# FinalSchematic1_0.net
KiCad netlist of a schematic drawn in EAGLE
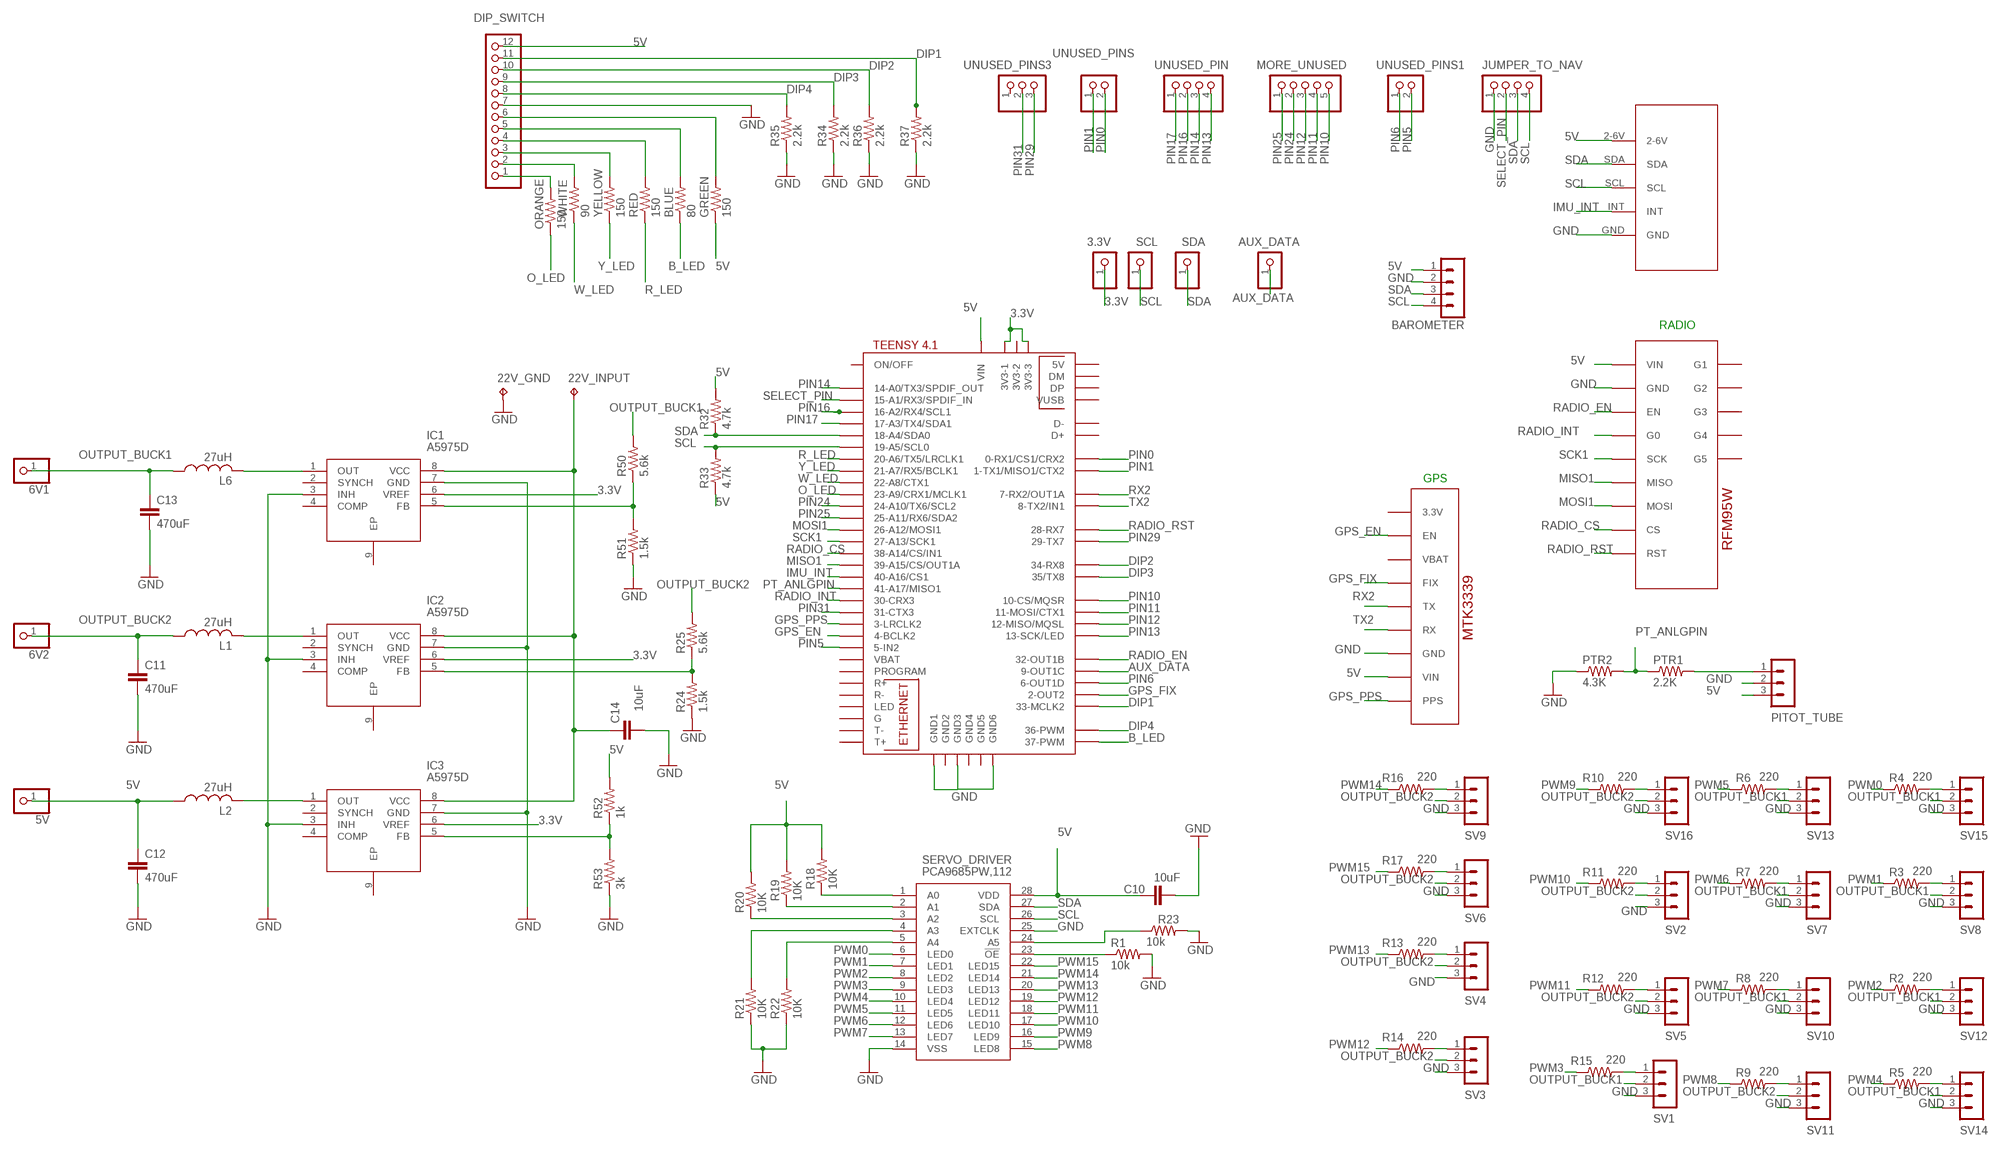
[diagram p0: schematic, sheet 1]

(export (version "E")
  (design (tool "Eeschema 10.0.6"))
  (components
    (comp (ref "3.3V")
      (value "PINHD-1X1")
      (footprint "eagle-import:1X01")
      (libsource (lib "eagle-import") (part "PINHD-1X1"))
    )
    (comp (ref "5V")
      (value "PINHD-1X1")
      (footprint "eagle-import:1X01")
      (libsource (lib "eagle-import") (part "PINHD-1X1"))
    )
    (comp (ref "6V1")
      (value "PINHD-1X1")
      (footprint "eagle-import:1X01")
      (libsource (lib "eagle-import") (part "PINHD-1X1"))
    )
    (comp (ref "6V2")
      (value "PINHD-1X1")
      (footprint "eagle-import:1X01")
      (libsource (lib "eagle-import") (part "PINHD-1X1"))
    )
    (comp (ref "22V_GND")
      (value "TPPAD1-17Y")
      (footprint "eagle-import:P1-17Y")
      (libsource (lib "eagle-import") (part "TPPAD1-17Y"))
    )
    (comp (ref "22V_INPUT")
      (value "TPPAD1-17Y")
      (footprint "eagle-import:P1-17Y")
      (libsource (lib "eagle-import") (part "TPPAD1-17Y"))
    )
    (comp (ref "AUX_DATA")
      (value "PINHD-1X1")
      (footprint "eagle-import:1X01")
      (libsource (lib "eagle-import") (part "PINHD-1X1"))
    )
    (comp (ref "BAROMETER")
      (value "MA04-1")
      (footprint "eagle-import:MA04-1")
      (libsource (lib "eagle-import") (part "MA04-1"))
    )
    (comp (ref "BLUE")
      (value "80")
      (footprint "eagle-import:0204_7")
      (libsource (lib "eagle-import") (part "R-US_0204/7"))
    )
    (comp (ref "C10")
      (value "10uF")
      (footprint "eagle-import:C2.5-3")
      (libsource (lib "eagle-import") (part "C2,5-3"))
    )
    (comp (ref "C11")
      (value "470uF")
      (footprint "eagle-import:C2.5-3")
      (libsource (lib "eagle-import") (part "C2,5-3"))
    )
    (comp (ref "C12")
      (value "470uF")
      (footprint "eagle-import:C2.5-3")
      (libsource (lib "eagle-import") (part "C2,5-3"))
    )
    (comp (ref "C13")
      (value "470uF")
      (footprint "eagle-import:C2.5-3")
      (libsource (lib "eagle-import") (part "C2,5-3"))
    )
    (comp (ref "C14")
      (value "10uF")
      (footprint "eagle-import:C2.5-3")
      (libsource (lib "eagle-import") (part "C2,5-3"))
    )
    (comp (ref "DIP_SWITCH")
      (value "PINHD-1X12")
      (footprint "eagle-import:1X12")
      (libsource (lib "eagle-import") (part "PINHD-1X12"))
    )
    (comp (ref "GPSMTK3339")
      (value "ADAFRUIT_MTK3339_GPS")
      (footprint "eagle-import:ADAFRUIT_MTK3339_GPS")
      (libsource (lib "eagle-import") (part "ADAFRUIT_MTK3339_GPS"))
    )
    (comp (ref "GREEN")
      (value "150")
      (footprint "eagle-import:0204_7")
      (libsource (lib "eagle-import") (part "R-US_0204/7"))
    )
    (comp (ref "IC1")
      (value "A5975D")
      (footprint "eagle-import:SOIC127P600X170-9N")
      (fields (field (name "MOUSER_PART_NUMBER") "511-A5975D"))
      (libsource (lib "eagle-import") (part "A5975D"))
    )
    (comp (ref "IC2")
      (value "A5975D")
      (footprint "eagle-import:SOIC127P600X170-9N")
      (fields (field (name "MOUSER_PART_NUMBER") "511-A5975D"))
      (libsource (lib "eagle-import") (part "A5975D"))
    )
    (comp (ref "IC3")
      (value "A5975D")
      (footprint "eagle-import:SOIC127P600X170-9N")
      (fields (field (name "MOUSER_PART_NUMBER") "511-A5975D"))
      (libsource (lib "eagle-import") (part "A5975D"))
    )
    (comp (ref "JUMPER_TO_NAV")
      (value "PINHD-1X4")
      (footprint "eagle-import:1X04")
      (libsource (lib "eagle-import") (part "PINHD-1X4"))
    )
    (comp (ref "L1")
      (value "27uH")
      (footprint "eagle-import:TFI0307")
      (libsource (lib "eagle-import") (part "L-USTFI0307"))
    )
    (comp (ref "L2")
      (value "27uH")
      (footprint "eagle-import:TFI0307")
      (libsource (lib "eagle-import") (part "L-USTFI0307"))
    )
    (comp (ref "L6")
      (value "27uH")
      (footprint "eagle-import:TFI0307")
      (libsource (lib "eagle-import") (part "L-USTFI0307"))
    )
    (comp (ref "MORE_UNUSED")
      (value "PINHD-1X5")
      (footprint "eagle-import:1X05")
      (libsource (lib "eagle-import") (part "PINHD-1X5"))
    )
    (comp (ref "ORANGE")
      (value "150")
      (footprint "eagle-import:0204_7")
      (libsource (lib "eagle-import") (part "R-US_0204/7"))
    )
    (comp (ref "PITOT_TUBE")
      (value "MA03-1")
      (footprint "eagle-import:MA03-1")
      (libsource (lib "eagle-import") (part "MA03-1"))
    )
    (comp (ref "PTR1")
      (value "2.2K")
      (footprint "eagle-import:0204_7")
      (libsource (lib "eagle-import") (part "R-US_0204/7"))
    )
    (comp (ref "PTR2")
      (value "4.3K")
      (footprint "eagle-import:0204_7")
      (libsource (lib "eagle-import") (part "R-US_0204/7"))
    )
    (comp (ref "R1")
      (value "10k")
      (footprint "eagle-import:0204_7")
      (libsource (lib "eagle-import") (part "R-US_0204/7"))
    )
    (comp (ref "R2")
      (value "220")
      (footprint "eagle-import:0204_7")
      (libsource (lib "eagle-import") (part "R-US_0204/7"))
    )
    (comp (ref "R3")
      (value "220")
      (footprint "eagle-import:0204_7")
      (libsource (lib "eagle-import") (part "R-US_0204/7"))
    )
    (comp (ref "R4")
      (value "220")
      (footprint "eagle-import:0204_7")
      (libsource (lib "eagle-import") (part "R-US_0204/7"))
    )
    (comp (ref "R5")
      (value "220")
      (footprint "eagle-import:0204_7")
      (libsource (lib "eagle-import") (part "R-US_0204/7"))
    )
    (comp (ref "R6")
      (value "220")
      (footprint "eagle-import:0204_7")
      (libsource (lib "eagle-import") (part "R-US_0204/7"))
    )
    (comp (ref "R7")
      (value "220")
      (footprint "eagle-import:0204_7")
      (libsource (lib "eagle-import") (part "R-US_0204/7"))
    )
    (comp (ref "R8")
      (value "220")
      (footprint "eagle-import:0204_7")
      (libsource (lib "eagle-import") (part "R-US_0204/7"))
    )
    (comp (ref "R9")
      (value "220")
      (footprint "eagle-import:0204_7")
      (libsource (lib "eagle-import") (part "R-US_0204/7"))
    )
    (comp (ref "R10")
      (value "220")
      (footprint "eagle-import:0204_7")
      (libsource (lib "eagle-import") (part "R-US_0204/7"))
    )
    (comp (ref "R11")
      (value "220")
      (footprint "eagle-import:0204_7")
      (libsource (lib "eagle-import") (part "R-US_0204/7"))
    )
    (comp (ref "R12")
      (value "220")
      (footprint "eagle-import:0204_7")
      (libsource (lib "eagle-import") (part "R-US_0204/7"))
    )
    (comp (ref "R13")
      (value "220")
      (footprint "eagle-import:0204_7")
      (libsource (lib "eagle-import") (part "R-US_0204/7"))
    )
    (comp (ref "R14")
      (value "220")
      (footprint "eagle-import:0204_7")
      (libsource (lib "eagle-import") (part "R-US_0204/7"))
    )
    (comp (ref "R15")
      (value "220")
      (footprint "eagle-import:0204_7")
      (libsource (lib "eagle-import") (part "R-US_0204/7"))
    )
    (comp (ref "R16")
      (value "220")
      (footprint "eagle-import:0204_7")
      (libsource (lib "eagle-import") (part "R-US_0204/7"))
    )
    (comp (ref "R17")
      (value "220")
      (footprint "eagle-import:0204_7")
      (libsource (lib "eagle-import") (part "R-US_0204/7"))
    )
    (comp (ref "R18")
      (value "10K")
      (footprint "eagle-import:0204_7")
      (libsource (lib "eagle-import") (part "R-US_0204/7"))
    )
    (comp (ref "R19")
      (value "10K")
      (footprint "eagle-import:0204_7")
      (libsource (lib "eagle-import") (part "R-US_0204/7"))
    )
    (comp (ref "R20")
      (value "10K")
      (footprint "eagle-import:0204_7")
      (libsource (lib "eagle-import") (part "R-US_0204/7"))
    )
    (comp (ref "R21")
      (value "10K")
      (footprint "eagle-import:0204_7")
      (libsource (lib "eagle-import") (part "R-US_0204/7"))
    )
    (comp (ref "R22")
      (value "10K")
      (footprint "eagle-import:0204_7")
      (libsource (lib "eagle-import") (part "R-US_0204/7"))
    )
    (comp (ref "R23")
      (value "10k")
      (footprint "eagle-import:0204_7")
      (libsource (lib "eagle-import") (part "R-US_0204/7"))
    )
    (comp (ref "R24")
      (value "1.5k")
      (footprint "eagle-import:0204_7")
      (libsource (lib "eagle-import") (part "R-US_0204/7"))
    )
    (comp (ref "R25")
      (value "5.6k")
      (footprint "eagle-import:0204_7")
      (libsource (lib "eagle-import") (part "R-US_0204/7"))
    )
    (comp (ref "R32")
      (value "4.7k")
      (footprint "eagle-import:0204_7")
      (libsource (lib "eagle-import") (part "R-US_0204/7"))
    )
    (comp (ref "R33")
      (value "4.7k")
      (footprint "eagle-import:0204_7")
      (libsource (lib "eagle-import") (part "R-US_0204/7"))
    )
    (comp (ref "R34")
      (value "2.2k")
      (footprint "eagle-import:0204_7")
      (libsource (lib "eagle-import") (part "R-US_0204/7"))
    )
    (comp (ref "R35")
      (value "2.2k")
      (footprint "eagle-import:0204_7")
      (libsource (lib "eagle-import") (part "R-US_0204/7"))
    )
    (comp (ref "R36")
      (value "2.2k")
      (footprint "eagle-import:0204_7")
      (libsource (lib "eagle-import") (part "R-US_0204/7"))
    )
    (comp (ref "R37")
      (value "2.2k")
      (footprint "eagle-import:0204_7")
      (libsource (lib "eagle-import") (part "R-US_0204/7"))
    )
    (comp (ref "R50")
      (value "5.6k")
      (footprint "eagle-import:0204_7")
      (libsource (lib "eagle-import") (part "R-US_0204/7"))
    )
    (comp (ref "R51")
      (value "1.5k")
      (footprint "eagle-import:0204_7")
      (libsource (lib "eagle-import") (part "R-US_0204/7"))
    )
    (comp (ref "R52")
      (value "1k")
      (footprint "eagle-import:0204_7")
      (libsource (lib "eagle-import") (part "R-US_0204/7"))
    )
    (comp (ref "R53")
      (value "3k")
      (footprint "eagle-import:0204_7")
      (libsource (lib "eagle-import") (part "R-US_0204/7"))
    )
    (comp (ref "RADIO")
      (value "ADAFRUIT_RFM95W_LORA_RADIO")
      (footprint "eagle-import:ADAFRUIT_RFM95W_LORA_RADIO")
      (libsource (lib "eagle-import") (part "ADAFRUIT_RFM95W_LORA_RADIO"))
    )
    (comp (ref "RED")
      (value "150")
      (footprint "eagle-import:0204_7")
      (libsource (lib "eagle-import") (part "R-US_0204/7"))
    )
    (comp (ref "SCL")
      (value "PINHD-1X1")
      (footprint "eagle-import:1X01")
      (libsource (lib "eagle-import") (part "PINHD-1X1"))
    )
    (comp (ref "SDA")
      (value "PINHD-1X1")
      (footprint "eagle-import:1X01")
      (libsource (lib "eagle-import") (part "PINHD-1X1"))
    )
    (comp (ref "SERVO_DRIVER")
      (value "PCA9685PW,112")
      (footprint "eagle-import:SOP65P640X110-28N")
      (fields (field (name "MOUSER_PART_NUMBER") "771-PCA9685PW,112"))
      (libsource (lib "eagle-import") (part "PCA9685PW,112"))
    )
    (comp (ref "SV1")
      (value "MA03-1")
      (footprint "eagle-import:MA03-1")
      (libsource (lib "eagle-import") (part "MA03-1"))
    )
    (comp (ref "SV2")
      (value "MA03-1")
      (footprint "eagle-import:MA03-1")
      (libsource (lib "eagle-import") (part "MA03-1"))
    )
    (comp (ref "SV3")
      (value "MA03-1")
      (footprint "eagle-import:MA03-1")
      (libsource (lib "eagle-import") (part "MA03-1"))
    )
    (comp (ref "SV4")
      (value "MA03-1")
      (footprint "eagle-import:MA03-1")
      (libsource (lib "eagle-import") (part "MA03-1"))
    )
    (comp (ref "SV5")
      (value "MA03-1")
      (footprint "eagle-import:MA03-1")
      (libsource (lib "eagle-import") (part "MA03-1"))
    )
    (comp (ref "SV6")
      (value "MA03-1")
      (footprint "eagle-import:MA03-1")
      (libsource (lib "eagle-import") (part "MA03-1"))
    )
    (comp (ref "SV7")
      (value "MA03-1")
      (footprint "eagle-import:MA03-1")
      (libsource (lib "eagle-import") (part "MA03-1"))
    )
    (comp (ref "SV8")
      (value "MA03-1")
      (footprint "eagle-import:MA03-1")
      (libsource (lib "eagle-import") (part "MA03-1"))
    )
    (comp (ref "SV9")
      (value "MA03-1")
      (footprint "eagle-import:MA03-1")
      (libsource (lib "eagle-import") (part "MA03-1"))
    )
    (comp (ref "SV10")
      (value "MA03-1")
      (footprint "eagle-import:MA03-1")
      (libsource (lib "eagle-import") (part "MA03-1"))
    )
    (comp (ref "SV11")
      (value "MA03-1")
      (footprint "eagle-import:MA03-1")
      (libsource (lib "eagle-import") (part "MA03-1"))
    )
    (comp (ref "SV12")
      (value "MA03-1")
      (footprint "eagle-import:MA03-1")
      (libsource (lib "eagle-import") (part "MA03-1"))
    )
    (comp (ref "SV13")
      (value "MA03-1")
      (footprint "eagle-import:MA03-1")
      (libsource (lib "eagle-import") (part "MA03-1"))
    )
    (comp (ref "SV14")
      (value "MA03-1")
      (footprint "eagle-import:MA03-1")
      (libsource (lib "eagle-import") (part "MA03-1"))
    )
    (comp (ref "SV15")
      (value "MA03-1")
      (footprint "eagle-import:MA03-1")
      (libsource (lib "eagle-import") (part "MA03-1"))
    )
    (comp (ref "SV16")
      (value "MA03-1")
      (footprint "eagle-import:MA03-1")
      (libsource (lib "eagle-import") (part "MA03-1"))
    )
    (comp (ref "TEENSY4.1")
      (value "TEENSY41")
      (footprint "eagle-import:TEENSY41")
      (libsource (lib "eagle-import") (part "TEENSY41"))
    )
    (comp (ref "U$2")
      (value "ICM20948BREAKOUTDEVICE")
      (footprint "eagle-import:ICM20948BREAKOUT")
      (libsource (lib "eagle-import") (part "ICM20948BREAKOUTDEVICE"))
    )
    (comp (ref "UNUSED_PIN")
      (value "PINHD-1X4")
      (footprint "eagle-import:1X04")
      (libsource (lib "eagle-import") (part "PINHD-1X4"))
    )
    (comp (ref "UNUSED_PINS")
      (value "PINHD-1X2")
      (footprint "eagle-import:1X02")
      (libsource (lib "eagle-import") (part "PINHD-1X2"))
    )
    (comp (ref "UNUSED_PINS1")
      (value "PINHD-1X2")
      (footprint "eagle-import:1X02")
      (libsource (lib "eagle-import") (part "PINHD-1X2"))
    )
    (comp (ref "UNUSED_PINS3")
      (value "PINHD-1X3")
      (footprint "eagle-import:1X03")
      (libsource (lib "eagle-import") (part "PINHD-1X3"))
    )
    (comp (ref "WHITE")
      (value "90")
      (footprint "eagle-import:0204_7")
      (libsource (lib "eagle-import") (part "R-US_0204/7"))
    )
    (comp (ref "YELLOW")
      (value "150")
      (footprint "eagle-import:0204_7")
      (libsource (lib "eagle-import") (part "R-US_0204/7"))
    )
  )
  (nets
    (net (code "1") (name "/3.3V") (class "Default")
      (node (ref "3.3V") (pin "1") (pinfunction "1_1") (pintype "passive"))
      (node (ref "IC1") (pin "6") (pinfunction "VREF_6") (pintype "bidirectional"))
      (node (ref "IC2") (pin "6") (pinfunction "VREF_6") (pintype "bidirectional"))
      (node (ref "IC3") (pin "6") (pinfunction "VREF_6") (pintype "bidirectional"))
      (node (ref "TEENSY4.1") (pin "3V3-1") (pinfunction "3V3-1_3V3-1") (pintype "bidirectional"))
      (node (ref "TEENSY4.1") (pin "3V3-3") (pinfunction "3V3-3_3V3-3") (pintype "bidirectional"))
    )
    (net (code "2") (name "/5V") (class "Default")
      (node (ref "5V") (pin "1") (pinfunction "1_1") (pintype "passive"))
      (node (ref "BAROMETER") (pin "1") (pinfunction "1_1") (pintype "passive"))
      (node (ref "C10") (pin "1") (pinfunction "1_1") (pintype "passive"))
      (node (ref "C12") (pin "1") (pinfunction "1_1") (pintype "passive"))
      (node (ref "DIP_SWITCH") (pin "12") (pinfunction "12_12") (pintype "passive"))
      (node (ref "GPSMTK3339") (pin "VIN") (pinfunction "VIN_VIN") (pintype "bidirectional"))
      (node (ref "GREEN") (pin "1") (pinfunction "1_1") (pintype "passive"))
      (node (ref "L2") (pin "1") (pinfunction "1_1") (pintype "passive"))
      (node (ref "PITOT_TUBE") (pin "3") (pinfunction "3_3") (pintype "passive"))
      (node (ref "R18") (pin "2") (pinfunction "2_2") (pintype "passive"))
      (node (ref "R19") (pin "2") (pinfunction "2_2") (pintype "passive"))
      (node (ref "R20") (pin "2") (pinfunction "2_2") (pintype "passive"))
      (node (ref "R32") (pin "2") (pinfunction "2_2") (pintype "passive"))
      (node (ref "R33") (pin "1") (pinfunction "1_1") (pintype "passive"))
      (node (ref "R52") (pin "2") (pinfunction "2_2") (pintype "passive"))
      (node (ref "RADIO") (pin "1") (pinfunction "VIN_1") (pintype "bidirectional"))
      (node (ref "SERVO_DRIVER") (pin "28") (pinfunction "VDD_28") (pintype "bidirectional"))
      (node (ref "TEENSY4.1") (pin "VIN") (pinfunction "VIN_VIN") (pintype "bidirectional"))
      (node (ref "U$2") (pin "2-6V") (pinfunction "2-6V_2-6V") (pintype "bidirectional"))
    )
    (net (code "3") (name "/AUX_DATA") (class "Default")
      (node (ref "AUX_DATA") (pin "1") (pinfunction "1_1") (pintype "passive"))
      (node (ref "TEENSY4.1") (pin "9-OUT1C") (pinfunction "9-OUT1C_9-OUT1C") (pintype "bidirectional"))
    )
    (net (code "4") (name "/B_LED") (class "Default")
      (node (ref "BLUE") (pin "1") (pinfunction "1_1") (pintype "passive"))
      (node (ref "TEENSY4.1") (pin "37-PWM") (pinfunction "37-PWM_37-PWM") (pintype "bidirectional"))
    )
    (net (code "5") (name "/DIP1") (class "Default")
      (node (ref "DIP_SWITCH") (pin "11") (pinfunction "11_11") (pintype "passive"))
      (node (ref "R37") (pin "2") (pinfunction "2_2") (pintype "passive"))
      (node (ref "TEENSY4.1") (pin "33-MCLK2") (pinfunction "33-MCLK2_33-MCLK2") (pintype "bidirectional"))
    )
    (net (code "6") (name "/DIP2") (class "Default")
      (node (ref "DIP_SWITCH") (pin "10") (pinfunction "10_10") (pintype "passive"))
      (node (ref "R36") (pin "2") (pinfunction "2_2") (pintype "passive"))
      (node (ref "TEENSY4.1") (pin "34-RX8") (pinfunction "34-RX8_34-RX8") (pintype "bidirectional"))
    )
    (net (code "7") (name "/DIP3") (class "Default")
      (node (ref "DIP_SWITCH") (pin "9") (pinfunction "9_9") (pintype "passive"))
      (node (ref "R34") (pin "2") (pinfunction "2_2") (pintype "passive"))
      (node (ref "TEENSY4.1") (pin "35-TX8") (pinfunction "35/TX8_35-TX8") (pintype "bidirectional"))
    )
    (net (code "8") (name "/DIP4") (class "Default")
      (node (ref "DIP_SWITCH") (pin "8") (pinfunction "8_8") (pintype "passive"))
      (node (ref "R35") (pin "2") (pinfunction "2_2") (pintype "passive"))
      (node (ref "TEENSY4.1") (pin "36-PWM") (pinfunction "36-PWM_36-PWM") (pintype "bidirectional"))
    )
    (net (code "9") (name "/GPS_EN") (class "Default")
      (node (ref "GPSMTK3339") (pin "EN") (pinfunction "EN_EN") (pintype "bidirectional"))
      (node (ref "TEENSY4.1") (pin "4-BCLK2") (pinfunction "4-BCLK2_4-BCLK2") (pintype "bidirectional"))
    )
    (net (code "10") (name "/GPS_FIX") (class "Default")
      (node (ref "GPSMTK3339") (pin "FIX") (pinfunction "FIX_FIX") (pintype "bidirectional"))
      (node (ref "TEENSY4.1") (pin "2-OUT2") (pinfunction "2-OUT2_2-OUT2") (pintype "bidirectional"))
    )
    (net (code "11") (name "/GPS_PPS") (class "Default")
      (node (ref "GPSMTK3339") (pin "PPS") (pinfunction "PPS_PPS") (pintype "bidirectional"))
      (node (ref "TEENSY4.1") (pin "3-LRCLK2") (pinfunction "3-LRCLK2_3-LRCLK2") (pintype "bidirectional"))
    )
    (net (code "12") (name "/IMU_INT") (class "Default")
      (node (ref "TEENSY4.1") (pin "40-A16/CS1") (pinfunction "40-A16/CS1_40-A16/CS1") (pintype "bidirectional"))
      (node (ref "U$2") (pin "INT") (pinfunction "INT_INT") (pintype "bidirectional"))
    )
    (net (code "13") (name "/MISO1") (class "Default")
      (node (ref "RADIO") (pin "6") (pinfunction "MISO_6") (pintype "bidirectional"))
      (node (ref "TEENSY4.1") (pin "39-A15/CS/OUT1A") (pinfunction "39-A15/CS/OUT1A_39-A15/CS/OUT1A") (pintype "bidirectional"))
    )
    (net (code "14") (name "/MOSI1") (class "Default")
      (node (ref "RADIO") (pin "7") (pinfunction "MOSI_7") (pintype "bidirectional"))
      (node (ref "TEENSY4.1") (pin "26-A12/MOSI1") (pinfunction "26-A12/MOSI1_26-A12/MOSI1") (pintype "bidirectional"))
    )
    (net (code "15") (name "/OUTPUT_BUCK1") (class "Default")
      (node (ref "6V1") (pin "1") (pinfunction "1_1") (pintype "passive"))
      (node (ref "C13") (pin "1") (pinfunction "1_1") (pintype "passive"))
      (node (ref "L6") (pin "1") (pinfunction "1_1") (pintype "passive"))
      (node (ref "R50") (pin "2") (pinfunction "2_2") (pintype "passive"))
      (node (ref "SV1") (pin "2") (pinfunction "2_2") (pintype "passive"))
      (node (ref "SV10") (pin "2") (pinfunction "2_2") (pintype "passive"))
      (node (ref "SV12") (pin "2") (pinfunction "2_2") (pintype "passive"))
      (node (ref "SV13") (pin "2") (pinfunction "2_2") (pintype "passive"))
      (node (ref "SV14") (pin "2") (pinfunction "2_2") (pintype "passive"))
      (node (ref "SV15") (pin "2") (pinfunction "2_2") (pintype "passive"))
      (node (ref "SV7") (pin "2") (pinfunction "2_2") (pintype "passive"))
      (node (ref "SV8") (pin "2") (pinfunction "2_2") (pintype "passive"))
    )
    (net (code "16") (name "/OUTPUT_BUCK2") (class "Default")
      (node (ref "6V2") (pin "1") (pinfunction "1_1") (pintype "passive"))
      (node (ref "C11") (pin "1") (pinfunction "1_1") (pintype "passive"))
      (node (ref "L1") (pin "1") (pinfunction "1_1") (pintype "passive"))
      (node (ref "R25") (pin "2") (pinfunction "2_2") (pintype "passive"))
      (node (ref "SV11") (pin "2") (pinfunction "2_2") (pintype "passive"))
      (node (ref "SV16") (pin "2") (pinfunction "2_2") (pintype "passive"))
      (node (ref "SV2") (pin "2") (pinfunction "2_2") (pintype "passive"))
      (node (ref "SV3") (pin "2") (pinfunction "2_2") (pintype "passive"))
      (node (ref "SV4") (pin "2") (pinfunction "2_2") (pintype "passive"))
      (node (ref "SV5") (pin "2") (pinfunction "2_2") (pintype "passive"))
      (node (ref "SV6") (pin "2") (pinfunction "2_2") (pintype "passive"))
      (node (ref "SV9") (pin "2") (pinfunction "2_2") (pintype "passive"))
    )
    (net (code "17") (name "/O_LED") (class "Default")
      (node (ref "ORANGE") (pin "1") (pinfunction "1_1") (pintype "passive"))
      (node (ref "TEENSY4.1") (pin "23-A9/CRX1/MCLK1") (pinfunction "23-A9/CRX1/MCLK1_23-A9/CRX1/MCLK1") (pintype "bidirectional"))
    )
    (net (code "18") (name "/PIN0") (class "Default")
      (node (ref "TEENSY4.1") (pin "0-RX1/CS1/CRX2") (pinfunction "0-RX1/CS1/CRX2_0-RX1/CS1/CRX2") (pintype "bidirectional"))
      (node (ref "UNUSED_PINS") (pin "2") (pinfunction "2_2") (pintype "passive"))
    )
    (net (code "19") (name "/PIN1") (class "Default")
      (node (ref "TEENSY4.1") (pin "1-TX1/MISO1/CTX2") (pinfunction "1-TX1/MISO1/CTX2_1-TX1/MISO1/CTX2") (pintype "bidirectional"))
      (node (ref "UNUSED_PINS") (pin "1") (pinfunction "1_1") (pintype "passive"))
    )
    (net (code "20") (name "/PIN5") (class "Default")
      (node (ref "TEENSY4.1") (pin "5-IN2") (pinfunction "5-IN2_5-IN2") (pintype "bidirectional"))
      (node (ref "UNUSED_PINS1") (pin "2") (pinfunction "2_2") (pintype "passive"))
    )
    (net (code "21") (name "/PIN6") (class "Default")
      (node (ref "TEENSY4.1") (pin "6-OUT1D") (pinfunction "6-OUT1D_6-OUT1D") (pintype "bidirectional"))
      (node (ref "UNUSED_PINS1") (pin "1") (pinfunction "1_1") (pintype "passive"))
    )
    (net (code "22") (name "/PIN10") (class "Default")
      (node (ref "MORE_UNUSED") (pin "5") (pinfunction "5_5") (pintype "passive"))
      (node (ref "TEENSY4.1") (pin "10-CS\\MQSR") (pinfunction "10-CS/MQSR_10-CS\\MQSR") (pintype "bidirectional"))
    )
    (net (code "23") (name "/PIN11") (class "Default")
      (node (ref "MORE_UNUSED") (pin "4") (pinfunction "4_4") (pintype "passive"))
      (node (ref "TEENSY4.1") (pin "11-MOSI/CTX1") (pinfunction "11-MOSI/CTX1_11-MOSI/CTX1") (pintype "bidirectional"))
    )
    (net (code "24") (name "/PIN12") (class "Default")
      (node (ref "MORE_UNUSED") (pin "3") (pinfunction "3_3") (pintype "passive"))
      (node (ref "TEENSY4.1") (pin "12-MISO/MQSL") (pinfunction "12-MISO/MQSL_12-MISO/MQSL") (pintype "bidirectional"))
    )
    (net (code "25") (name "/PIN13") (class "Default")
      (node (ref "TEENSY4.1") (pin "13-SCK/LED") (pinfunction "13-SCK/LED_13-SCK/LED") (pintype "bidirectional"))
      (node (ref "UNUSED_PIN") (pin "4") (pinfunction "4_4") (pintype "passive"))
    )
    (net (code "26") (name "/PIN14") (class "Default")
      (node (ref "TEENSY4.1") (pin "14-A0/TX3/SPDIF_OUT") (pinfunction "14-A0/TX3/SPDIF_OUT_14-A0/TX3/SPDIF_OUT") (pintype "bidirectional"))
      (node (ref "UNUSED_PIN") (pin "3") (pinfunction "3_3") (pintype "passive"))
    )
    (net (code "27") (name "/PIN16") (class "Default")
      (node (ref "TEENSY4.1") (pin "16-A2/RX4/SCL1") (pinfunction "16-A2/RX4/SCL1_16-A2/RX4/SCL1") (pintype "bidirectional"))
      (node (ref "UNUSED_PIN") (pin "2") (pinfunction "2_2") (pintype "passive"))
    )
    (net (code "28") (name "/PIN17") (class "Default")
      (node (ref "TEENSY4.1") (pin "17-A3/TX4/SDA1") (pinfunction "17-A3/TX4/SDA1_17-A3/TX4/SDA1") (pintype "bidirectional"))
      (node (ref "UNUSED_PIN") (pin "1") (pinfunction "1_1") (pintype "passive"))
    )
    (net (code "29") (name "/PIN24") (class "Default")
      (node (ref "MORE_UNUSED") (pin "2") (pinfunction "2_2") (pintype "passive"))
      (node (ref "TEENSY4.1") (pin "24-A10/TX6/SCL2") (pinfunction "24-A10/TX6/SCL2_24-A10/TX6/SCL2") (pintype "bidirectional"))
    )
    (net (code "30") (name "/PIN25") (class "Default")
      (node (ref "MORE_UNUSED") (pin "1") (pinfunction "1_1") (pintype "passive"))
      (node (ref "TEENSY4.1") (pin "25-A11/RX6/SDA2") (pinfunction "25-A11/RX6/SDA2_25-A11/RX6/SDA2") (pintype "bidirectional"))
    )
    (net (code "31") (name "/PIN29") (class "Default")
      (node (ref "TEENSY4.1") (pin "29-TX7") (pinfunction "29-TX7_29-TX7") (pintype "bidirectional"))
      (node (ref "UNUSED_PINS3") (pin "3") (pinfunction "3_3") (pintype "passive"))
    )
    (net (code "32") (name "/PIN31") (class "Default")
      (node (ref "TEENSY4.1") (pin "31-CTX3") (pinfunction "31-CTX3_31-CTX3") (pintype "bidirectional"))
      (node (ref "UNUSED_PINS3") (pin "2") (pinfunction "2_2") (pintype "passive"))
    )
    (net (code "33") (name "/PT_ANLGPIN") (class "Default")
      (node (ref "PTR1") (pin "1") (pinfunction "1_1") (pintype "passive"))
      (node (ref "PTR2") (pin "2") (pinfunction "2_2") (pintype "passive"))
      (node (ref "TEENSY4.1") (pin "41-A17/MISO1") (pinfunction "41-A17/MISO1_41-A17/MISO1") (pintype "bidirectional"))
    )
    (net (code "34") (name "/PWM0") (class "Default")
      (node (ref "R4") (pin "1") (pinfunction "1_1") (pintype "passive"))
      (node (ref "SERVO_DRIVER") (pin "6") (pinfunction "LED0_6") (pintype "bidirectional"))
    )
    (net (code "35") (name "/PWM1") (class "Default")
      (node (ref "R3") (pin "1") (pinfunction "1_1") (pintype "passive"))
      (node (ref "SERVO_DRIVER") (pin "7") (pinfunction "LED1_7") (pintype "bidirectional"))
    )
    (net (code "36") (name "/PWM2") (class "Default")
      (node (ref "R2") (pin "1") (pinfunction "1_1") (pintype "passive"))
      (node (ref "SERVO_DRIVER") (pin "8") (pinfunction "LED2_8") (pintype "bidirectional"))
    )
    (net (code "37") (name "/PWM3") (class "Default")
      (node (ref "R15") (pin "1") (pinfunction "1_1") (pintype "passive"))
      (node (ref "SERVO_DRIVER") (pin "9") (pinfunction "LED3_9") (pintype "bidirectional"))
    )
    (net (code "38") (name "/PWM4") (class "Default")
      (node (ref "R5") (pin "1") (pinfunction "1_1") (pintype "passive"))
      (node (ref "SERVO_DRIVER") (pin "10") (pinfunction "LED4_10") (pintype "bidirectional"))
    )
    (net (code "39") (name "/PWM5") (class "Default")
      (node (ref "R6") (pin "1") (pinfunction "1_1") (pintype "passive"))
      (node (ref "SERVO_DRIVER") (pin "11") (pinfunction "LED5_11") (pintype "bidirectional"))
    )
    (net (code "40") (name "/PWM6") (class "Default")
      (node (ref "R7") (pin "1") (pinfunction "1_1") (pintype "passive"))
      (node (ref "SERVO_DRIVER") (pin "12") (pinfunction "LED6_12") (pintype "bidirectional"))
    )
    (net (code "41") (name "/PWM7") (class "Default")
      (node (ref "R8") (pin "1") (pinfunction "1_1") (pintype "passive"))
      (node (ref "SERVO_DRIVER") (pin "13") (pinfunction "LED7_13") (pintype "bidirectional"))
    )
    (net (code "42") (name "/PWM8") (class "Default")
      (node (ref "R9") (pin "1") (pinfunction "1_1") (pintype "passive"))
      (node (ref "SERVO_DRIVER") (pin "15") (pinfunction "LED8_15") (pintype "bidirectional"))
    )
    (net (code "43") (name "/PWM9") (class "Default")
      (node (ref "R10") (pin "1") (pinfunction "1_1") (pintype "passive"))
      (node (ref "SERVO_DRIVER") (pin "16") (pinfunction "LED9_16") (pintype "bidirectional"))
    )
    (net (code "44") (name "/PWM10") (class "Default")
      (node (ref "R11") (pin "1") (pinfunction "1_1") (pintype "passive"))
      (node (ref "SERVO_DRIVER") (pin "17") (pinfunction "LED10_17") (pintype "bidirectional"))
    )
    (net (code "45") (name "/PWM11") (class "Default")
      (node (ref "R12") (pin "1") (pinfunction "1_1") (pintype "passive"))
      (node (ref "SERVO_DRIVER") (pin "18") (pinfunction "LED11_18") (pintype "bidirectional"))
    )
    (net (code "46") (name "/PWM12") (class "Default")
      (node (ref "R14") (pin "1") (pinfunction "1_1") (pintype "passive"))
      (node (ref "SERVO_DRIVER") (pin "19") (pinfunction "LED12_19") (pintype "bidirectional"))
    )
    (net (code "47") (name "/PWM13") (class "Default")
      (node (ref "R13") (pin "1") (pinfunction "1_1") (pintype "passive"))
      (node (ref "SERVO_DRIVER") (pin "20") (pinfunction "LED13_20") (pintype "bidirectional"))
    )
    (net (code "48") (name "/PWM14") (class "Default")
      (node (ref "R16") (pin "1") (pinfunction "1_1") (pintype "passive"))
      (node (ref "SERVO_DRIVER") (pin "21") (pinfunction "LED14_21") (pintype "bidirectional"))
    )
    (net (code "49") (name "/PWM15") (class "Default")
      (node (ref "R17") (pin "1") (pinfunction "1_1") (pintype "passive"))
      (node (ref "SERVO_DRIVER") (pin "22") (pinfunction "LED15_22") (pintype "bidirectional"))
    )
    (net (code "50") (name "/RADIO_CS") (class "Default")
      (node (ref "RADIO") (pin "8") (pinfunction "CS_8") (pintype "bidirectional"))
      (node (ref "TEENSY4.1") (pin "38-A14/CS/IN1") (pinfunction "38-A14/CS/IN1_38-A14/CS/IN1") (pintype "bidirectional"))
    )
    (net (code "51") (name "/RADIO_EN") (class "Default")
      (node (ref "RADIO") (pin "3") (pinfunction "EN_3") (pintype "bidirectional"))
      (node (ref "TEENSY4.1") (pin "32-OUT1B") (pinfunction "32-OUT1B_32-OUT1B") (pintype "bidirectional"))
    )
    (net (code "52") (name "/RADIO_INT") (class "Default")
      (node (ref "RADIO") (pin "4") (pinfunction "G0_4") (pintype "bidirectional"))
      (node (ref "TEENSY4.1") (pin "30-CRX3") (pinfunction "30-CRX3_30-CRX3") (pintype "bidirectional"))
    )
    (net (code "53") (name "/RADIO_RST") (class "Default")
      (node (ref "RADIO") (pin "9") (pinfunction "RST_9") (pintype "bidirectional"))
      (node (ref "TEENSY4.1") (pin "28-RX7") (pinfunction "28-RX7_28-RX7") (pintype "bidirectional"))
    )
    (net (code "54") (name "/RX2") (class "Default")
      (node (ref "GPSMTK3339") (pin "TX") (pinfunction "TX_TX") (pintype "bidirectional"))
      (node (ref "TEENSY4.1") (pin "7-RX2/OUT1A") (pinfunction "7-RX2/OUT1A_7-RX2/OUT1A") (pintype "bidirectional"))
    )
    (net (code "55") (name "/R_LED") (class "Default")
      (node (ref "RED") (pin "1") (pinfunction "1_1") (pintype "passive"))
      (node (ref "TEENSY4.1") (pin "20-A6/TX5/LRCLK1") (pinfunction "20-A6/TX5/LRCLK1_20-A6/TX5/LRCLK1") (pintype "bidirectional"))
    )
    (net (code "56") (name "/SCK1") (class "Default")
      (node (ref "RADIO") (pin "5") (pinfunction "SCK_5") (pintype "bidirectional"))
      (node (ref "TEENSY4.1") (pin "27-A13/SCK1") (pinfunction "27-A13/SCK1_27-A13/SCK1") (pintype "bidirectional"))
    )
    (net (code "57") (name "/SCL") (class "Default")
      (node (ref "BAROMETER") (pin "4") (pinfunction "4_4") (pintype "passive"))
      (node (ref "JUMPER_TO_NAV") (pin "4") (pinfunction "4_4") (pintype "passive"))
      (node (ref "R33") (pin "2") (pinfunction "2_2") (pintype "passive"))
      (node (ref "SCL") (pin "1") (pinfunction "1_1") (pintype "passive"))
      (node (ref "SERVO_DRIVER") (pin "26") (pinfunction "SCL_26") (pintype "bidirectional"))
      (node (ref "TEENSY4.1") (pin "19-A5/SCL0") (pinfunction "19-A5/SCL0_19-A5/SCL0") (pintype "bidirectional"))
      (node (ref "U$2") (pin "SCL") (pinfunction "SCL_SCL") (pintype "bidirectional"))
    )
    (net (code "58") (name "/SDA") (class "Default")
      (node (ref "BAROMETER") (pin "3") (pinfunction "3_3") (pintype "passive"))
      (node (ref "JUMPER_TO_NAV") (pin "3") (pinfunction "3_3") (pintype "passive"))
      (node (ref "R32") (pin "1") (pinfunction "1_1") (pintype "passive"))
      (node (ref "SDA") (pin "1") (pinfunction "1_1") (pintype "passive"))
      (node (ref "SERVO_DRIVER") (pin "27") (pinfunction "SDA_27") (pintype "bidirectional"))
      (node (ref "TEENSY4.1") (pin "18-A4/SDA0") (pinfunction "18-A4/SDA0_18-A4/SDA0") (pintype "bidirectional"))
      (node (ref "U$2") (pin "SDA") (pinfunction "SDA_SDA") (pintype "bidirectional"))
    )
    (net (code "59") (name "/SELECT_PIN") (class "Default")
      (node (ref "JUMPER_TO_NAV") (pin "2") (pinfunction "2_2") (pintype "passive"))
      (node (ref "TEENSY4.1") (pin "15-A1/RX3/SPDIF_IN") (pinfunction "15-A1/RX3/SPDIF_IN_15-A1/RX3/SPDIF_IN") (pintype "bidirectional"))
    )
    (net (code "60") (name "/TX2") (class "Default")
      (node (ref "GPSMTK3339") (pin "RX") (pinfunction "RX_RX") (pintype "bidirectional"))
      (node (ref "TEENSY4.1") (pin "8-TX2/IN1") (pinfunction "8-TX2/IN1_8-TX2/IN1") (pintype "bidirectional"))
    )
    (net (code "61") (name "/W_LED") (class "Default")
      (node (ref "TEENSY4.1") (pin "22-A8/CTX1") (pinfunction "22-A8/CTX1_22-A8/CTX1") (pintype "bidirectional"))
      (node (ref "WHITE") (pin "1") (pinfunction "1_1") (pintype "passive"))
    )
    (net (code "62") (name "/Y_LED") (class "Default")
      (node (ref "TEENSY4.1") (pin "21-A7/RX5/BCLK1") (pinfunction "21-A7/RX5/BCLK1_21-A7/RX5/BCLK1") (pintype "bidirectional"))
      (node (ref "YELLOW") (pin "1") (pinfunction "1_1") (pintype "passive"))
    )
    (net (code "63") (name "GND") (class "Default")
      (node (ref "22V_GND") (pin "TP") (pinfunction "TP_TP") (pintype "input"))
      (node (ref "BAROMETER") (pin "2") (pinfunction "2_2") (pintype "passive"))
      (node (ref "C10") (pin "2") (pinfunction "2_2") (pintype "passive"))
      (node (ref "C11") (pin "2") (pinfunction "2_2") (pintype "passive"))
      (node (ref "C12") (pin "2") (pinfunction "2_2") (pintype "passive"))
      (node (ref "C13") (pin "2") (pinfunction "2_2") (pintype "passive"))
      (node (ref "C14") (pin "2") (pinfunction "2_2") (pintype "passive"))
      (node (ref "DIP_SWITCH") (pin "7") (pinfunction "7_7") (pintype "passive"))
      (node (ref "GPSMTK3339") (pin "GND") (pinfunction "GND_GND") (pintype "bidirectional"))
      (node (ref "IC1") (pin "3") (pinfunction "INH_3") (pintype "bidirectional"))
      (node (ref "IC1") (pin "7") (pinfunction "GND_7") (pintype "bidirectional"))
      (node (ref "IC2") (pin "3") (pinfunction "INH_3") (pintype "bidirectional"))
      (node (ref "IC2") (pin "7") (pinfunction "GND_7") (pintype "bidirectional"))
      (node (ref "IC3") (pin "3") (pinfunction "INH_3") (pintype "bidirectional"))
      (node (ref "IC3") (pin "7") (pinfunction "GND_7") (pintype "bidirectional"))
      (node (ref "JUMPER_TO_NAV") (pin "1") (pinfunction "1_1") (pintype "passive"))
      (node (ref "PITOT_TUBE") (pin "2") (pinfunction "2_2") (pintype "passive"))
      (node (ref "PTR2") (pin "1") (pinfunction "1_1") (pintype "passive"))
      (node (ref "R1") (pin "2") (pinfunction "2_2") (pintype "passive"))
      (node (ref "R21") (pin "1") (pinfunction "1_1") (pintype "passive"))
      (node (ref "R22") (pin "1") (pinfunction "1_1") (pintype "passive"))
      (node (ref "R23") (pin "2") (pinfunction "2_2") (pintype "passive"))
      (node (ref "R24") (pin "1") (pinfunction "1_1") (pintype "passive"))
      (node (ref "R34") (pin "1") (pinfunction "1_1") (pintype "passive"))
      (node (ref "R35") (pin "1") (pinfunction "1_1") (pintype "passive"))
      (node (ref "R36") (pin "1") (pinfunction "1_1") (pintype "passive"))
      (node (ref "R37") (pin "1") (pinfunction "1_1") (pintype "passive"))
      (node (ref "R51") (pin "1") (pinfunction "1_1") (pintype "passive"))
      (node (ref "R53") (pin "1") (pinfunction "1_1") (pintype "passive"))
      (node (ref "RADIO") (pin "2") (pinfunction "GND_2") (pintype "bidirectional"))
      (node (ref "SERVO_DRIVER") (pin "14") (pinfunction "VSS_14") (pintype "bidirectional"))
      (node (ref "SERVO_DRIVER") (pin "25") (pinfunction "EXTCLK_25") (pintype "bidirectional"))
      (node (ref "SV1") (pin "3") (pinfunction "3_3") (pintype "passive"))
      (node (ref "SV10") (pin "3") (pinfunction "3_3") (pintype "passive"))
      (node (ref "SV11") (pin "3") (pinfunction "3_3") (pintype "passive"))
      (node (ref "SV12") (pin "3") (pinfunction "3_3") (pintype "passive"))
      (node (ref "SV13") (pin "3") (pinfunction "3_3") (pintype "passive"))
      (node (ref "SV14") (pin "3") (pinfunction "3_3") (pintype "passive"))
      (node (ref "SV15") (pin "3") (pinfunction "3_3") (pintype "passive"))
      (node (ref "SV16") (pin "3") (pinfunction "3_3") (pintype "passive"))
      (node (ref "SV2") (pin "3") (pinfunction "3_3") (pintype "passive"))
      (node (ref "SV3") (pin "3") (pinfunction "3_3") (pintype "passive"))
      (node (ref "SV4") (pin "3") (pinfunction "3_3") (pintype "passive"))
      (node (ref "SV5") (pin "3") (pinfunction "3_3") (pintype "passive"))
      (node (ref "SV6") (pin "3") (pinfunction "3_3") (pintype "passive"))
      (node (ref "SV7") (pin "3") (pinfunction "3_3") (pintype "passive"))
      (node (ref "SV8") (pin "3") (pinfunction "3_3") (pintype "passive"))
      (node (ref "SV9") (pin "3") (pinfunction "3_3") (pintype "passive"))
      (node (ref "TEENSY4.1") (pin "GND1") (pinfunction "GND1_GND1") (pintype "bidirectional"))
      (node (ref "TEENSY4.1") (pin "GND3") (pinfunction "GND3_GND3") (pintype "bidirectional"))
      (node (ref "TEENSY4.1") (pin "GND6") (pinfunction "GND6_GND6") (pintype "bidirectional"))
      (node (ref "U$2") (pin "GND") (pinfunction "GND_GND") (pintype "bidirectional"))
    )
    (net (code "64") (name "Net-(BLUE-Pad2)") (class "Default")
      (node (ref "BLUE") (pin "2") (pinfunction "2_2") (pintype "passive"))
      (node (ref "DIP_SWITCH") (pin "5") (pinfunction "5_5") (pintype "passive"))
    )
    (net (code "65") (name "Net-(DIP_SWITCH-Pad1)") (class "Default")
      (node (ref "DIP_SWITCH") (pin "1") (pinfunction "1_1") (pintype "passive"))
      (node (ref "ORANGE") (pin "2") (pinfunction "2_2") (pintype "passive"))
    )
    (net (code "66") (name "Net-(DIP_SWITCH-Pad2)") (class "Default")
      (node (ref "DIP_SWITCH") (pin "2") (pinfunction "2_2") (pintype "passive"))
      (node (ref "WHITE") (pin "2") (pinfunction "2_2") (pintype "passive"))
    )
    (net (code "67") (name "Net-(DIP_SWITCH-Pad3)") (class "Default")
      (node (ref "DIP_SWITCH") (pin "3") (pinfunction "3_3") (pintype "passive"))
      (node (ref "YELLOW") (pin "2") (pinfunction "2_2") (pintype "passive"))
    )
    (net (code "68") (name "Net-(DIP_SWITCH-Pad4)") (class "Default")
      (node (ref "DIP_SWITCH") (pin "4") (pinfunction "4_4") (pintype "passive"))
      (node (ref "RED") (pin "2") (pinfunction "2_2") (pintype "passive"))
    )
    (net (code "69") (name "Net-(DIP_SWITCH-Pad6)") (class "Default")
      (node (ref "DIP_SWITCH") (pin "6") (pinfunction "6_6") (pintype "passive"))
      (node (ref "GREEN") (pin "2") (pinfunction "2_2") (pintype "passive"))
    )
    (net (code "70") (name "Net-(IC1-FB)") (class "Default")
      (node (ref "IC1") (pin "5") (pinfunction "FB_5") (pintype "bidirectional"))
      (node (ref "R50") (pin "1") (pinfunction "1_1") (pintype "passive"))
      (node (ref "R51") (pin "2") (pinfunction "2_2") (pintype "passive"))
    )
    (net (code "71") (name "Net-(IC1-OUT)") (class "Default")
      (node (ref "IC1") (pin "1") (pinfunction "OUT_1") (pintype "bidirectional"))
      (node (ref "L6") (pin "2") (pinfunction "2_2") (pintype "passive"))
    )
    (net (code "72") (name "Net-(IC1-VCC)") (class "Default")
      (node (ref "22V_INPUT") (pin "TP") (pinfunction "TP_TP") (pintype "input"))
      (node (ref "C14") (pin "1") (pinfunction "1_1") (pintype "passive"))
      (node (ref "IC1") (pin "8") (pinfunction "VCC_8") (pintype "bidirectional"))
      (node (ref "IC2") (pin "8") (pinfunction "VCC_8") (pintype "bidirectional"))
      (node (ref "IC3") (pin "8") (pinfunction "VCC_8") (pintype "bidirectional"))
    )
    (net (code "73") (name "Net-(IC2-FB)") (class "Default")
      (node (ref "IC2") (pin "5") (pinfunction "FB_5") (pintype "bidirectional"))
      (node (ref "R24") (pin "2") (pinfunction "2_2") (pintype "passive"))
      (node (ref "R25") (pin "1") (pinfunction "1_1") (pintype "passive"))
    )
    (net (code "74") (name "Net-(IC2-OUT)") (class "Default")
      (node (ref "IC2") (pin "1") (pinfunction "OUT_1") (pintype "bidirectional"))
      (node (ref "L1") (pin "2") (pinfunction "2_2") (pintype "passive"))
    )
    (net (code "75") (name "Net-(IC3-FB)") (class "Default")
      (node (ref "IC3") (pin "5") (pinfunction "FB_5") (pintype "bidirectional"))
      (node (ref "R52") (pin "1") (pinfunction "1_1") (pintype "passive"))
      (node (ref "R53") (pin "2") (pinfunction "2_2") (pintype "passive"))
    )
    (net (code "76") (name "Net-(IC3-OUT)") (class "Default")
      (node (ref "IC3") (pin "1") (pinfunction "OUT_1") (pintype "bidirectional"))
      (node (ref "L2") (pin "2") (pinfunction "2_2") (pintype "passive"))
    )
    (net (code "77") (name "Net-(PITOT_TUBE-Pad1)") (class "Default")
      (node (ref "PITOT_TUBE") (pin "1") (pinfunction "1_1") (pintype "passive"))
      (node (ref "PTR1") (pin "2") (pinfunction "2_2") (pintype "passive"))
    )
    (net (code "78") (name "Net-(R2-Pad2)") (class "Default")
      (node (ref "R2") (pin "2") (pinfunction "2_2") (pintype "passive"))
      (node (ref "SV12") (pin "1") (pinfunction "1_1") (pintype "passive"))
    )
    (net (code "79") (name "Net-(R3-Pad2)") (class "Default")
      (node (ref "R3") (pin "2") (pinfunction "2_2") (pintype "passive"))
      (node (ref "SV8") (pin "1") (pinfunction "1_1") (pintype "passive"))
    )
    (net (code "80") (name "Net-(R4-Pad2)") (class "Default")
      (node (ref "R4") (pin "2") (pinfunction "2_2") (pintype "passive"))
      (node (ref "SV15") (pin "1") (pinfunction "1_1") (pintype "passive"))
    )
    (net (code "81") (name "Net-(R5-Pad2)") (class "Default")
      (node (ref "R5") (pin "2") (pinfunction "2_2") (pintype "passive"))
      (node (ref "SV14") (pin "1") (pinfunction "1_1") (pintype "passive"))
    )
    (net (code "82") (name "Net-(R6-Pad2)") (class "Default")
      (node (ref "R6") (pin "2") (pinfunction "2_2") (pintype "passive"))
      (node (ref "SV13") (pin "1") (pinfunction "1_1") (pintype "passive"))
    )
    (net (code "83") (name "Net-(R7-Pad2)") (class "Default")
      (node (ref "R7") (pin "2") (pinfunction "2_2") (pintype "passive"))
      (node (ref "SV7") (pin "1") (pinfunction "1_1") (pintype "passive"))
    )
    (net (code "84") (name "Net-(R8-Pad2)") (class "Default")
      (node (ref "R8") (pin "2") (pinfunction "2_2") (pintype "passive"))
      (node (ref "SV10") (pin "1") (pinfunction "1_1") (pintype "passive"))
    )
    (net (code "85") (name "Net-(R9-Pad2)") (class "Default")
      (node (ref "R9") (pin "2") (pinfunction "2_2") (pintype "passive"))
      (node (ref "SV11") (pin "1") (pinfunction "1_1") (pintype "passive"))
    )
    (net (code "86") (name "Net-(R10-Pad2)") (class "Default")
      (node (ref "R10") (pin "2") (pinfunction "2_2") (pintype "passive"))
      (node (ref "SV16") (pin "1") (pinfunction "1_1") (pintype "passive"))
    )
    (net (code "87") (name "Net-(R11-Pad2)") (class "Default")
      (node (ref "R11") (pin "2") (pinfunction "2_2") (pintype "passive"))
      (node (ref "SV2") (pin "1") (pinfunction "1_1") (pintype "passive"))
    )
    (net (code "88") (name "Net-(R12-Pad2)") (class "Default")
      (node (ref "R12") (pin "2") (pinfunction "2_2") (pintype "passive"))
      (node (ref "SV5") (pin "1") (pinfunction "1_1") (pintype "passive"))
    )
    (net (code "89") (name "Net-(R13-Pad2)") (class "Default")
      (node (ref "R13") (pin "2") (pinfunction "2_2") (pintype "passive"))
      (node (ref "SV4") (pin "1") (pinfunction "1_1") (pintype "passive"))
    )
    (net (code "90") (name "Net-(R14-Pad2)") (class "Default")
      (node (ref "R14") (pin "2") (pinfunction "2_2") (pintype "passive"))
      (node (ref "SV3") (pin "1") (pinfunction "1_1") (pintype "passive"))
    )
    (net (code "91") (name "Net-(R15-Pad2)") (class "Default")
      (node (ref "R15") (pin "2") (pinfunction "2_2") (pintype "passive"))
      (node (ref "SV1") (pin "1") (pinfunction "1_1") (pintype "passive"))
    )
    (net (code "92") (name "Net-(R16-Pad2)") (class "Default")
      (node (ref "R16") (pin "2") (pinfunction "2_2") (pintype "passive"))
      (node (ref "SV9") (pin "1") (pinfunction "1_1") (pintype "passive"))
    )
    (net (code "93") (name "Net-(R17-Pad2)") (class "Default")
      (node (ref "R17") (pin "2") (pinfunction "2_2") (pintype "passive"))
      (node (ref "SV6") (pin "1") (pinfunction "1_1") (pintype "passive"))
    )
    (net (code "94") (name "Net-(SERVO_DRIVER-A0)") (class "Default")
      (node (ref "R18") (pin "1") (pinfunction "1_1") (pintype "passive"))
      (node (ref "SERVO_DRIVER") (pin "1") (pinfunction "A0_1") (pintype "bidirectional"))
    )
    (net (code "95") (name "Net-(SERVO_DRIVER-A1)") (class "Default")
      (node (ref "R19") (pin "1") (pinfunction "1_1") (pintype "passive"))
      (node (ref "SERVO_DRIVER") (pin "2") (pinfunction "A1_2") (pintype "bidirectional"))
    )
    (net (code "96") (name "Net-(SERVO_DRIVER-A2)") (class "Default")
      (node (ref "R20") (pin "1") (pinfunction "1_1") (pintype "passive"))
      (node (ref "SERVO_DRIVER") (pin "3") (pinfunction "A2_3") (pintype "bidirectional"))
    )
    (net (code "97") (name "Net-(SERVO_DRIVER-A3)") (class "Default")
      (node (ref "R21") (pin "2") (pinfunction "2_2") (pintype "passive"))
      (node (ref "SERVO_DRIVER") (pin "4") (pinfunction "A3_4") (pintype "bidirectional"))
    )
    (net (code "98") (name "Net-(SERVO_DRIVER-A4)") (class "Default")
      (node (ref "R22") (pin "2") (pinfunction "2_2") (pintype "passive"))
      (node (ref "SERVO_DRIVER") (pin "5") (pinfunction "A4_5") (pintype "bidirectional"))
    )
    (net (code "99") (name "Net-(SERVO_DRIVER-A5)") (class "Default")
      (node (ref "R23") (pin "1") (pinfunction "1_1") (pintype "passive"))
      (node (ref "SERVO_DRIVER") (pin "24") (pinfunction "A5_24") (pintype "bidirectional"))
    )
    (net (code "100") (name "Net-(SERVO_DRIVER-~{OE})") (class "Default")
      (node (ref "R1") (pin "1") (pinfunction "1_1") (pintype "passive"))
      (node (ref "SERVO_DRIVER") (pin "23") (pinfunction "~{OE}_23") (pintype "bidirectional"))
    )
    (net (code "101") (name "unconnected-(GPSMTK3339-Pad3.3V)") (class "Default")
      (node (ref "GPSMTK3339") (pin "3.3V") (pinfunction "3.3V_3.3V") (pintype "bidirectional"))
    )
    (net (code "102") (name "unconnected-(GPSMTK3339-PadVBAT)") (class "Default")
      (node (ref "GPSMTK3339") (pin "VBAT") (pinfunction "VBAT_VBAT") (pintype "bidirectional"))
    )
    (net (code "103") (name "unconnected-(IC1-COMP-Pad4)") (class "Default")
      (node (ref "IC1") (pin "4") (pinfunction "COMP_4") (pintype "bidirectional"))
    )
    (net (code "104") (name "unconnected-(IC1-EP-Pad9)") (class "Default")
      (node (ref "IC1") (pin "9") (pinfunction "EP_9") (pintype "bidirectional"))
    )
    (net (code "105") (name "unconnected-(IC1-SYNCH-Pad2)") (class "Default")
      (node (ref "IC1") (pin "2") (pinfunction "SYNCH_2") (pintype "bidirectional"))
    )
    (net (code "106") (name "unconnected-(IC2-COMP-Pad4)") (class "Default")
      (node (ref "IC2") (pin "4") (pinfunction "COMP_4") (pintype "bidirectional"))
    )
    (net (code "107") (name "unconnected-(IC2-EP-Pad9)") (class "Default")
      (node (ref "IC2") (pin "9") (pinfunction "EP_9") (pintype "bidirectional"))
    )
    (net (code "108") (name "unconnected-(IC2-SYNCH-Pad2)") (class "Default")
      (node (ref "IC2") (pin "2") (pinfunction "SYNCH_2") (pintype "bidirectional"))
    )
    (net (code "109") (name "unconnected-(IC3-COMP-Pad4)") (class "Default")
      (node (ref "IC3") (pin "4") (pinfunction "COMP_4") (pintype "bidirectional"))
    )
    (net (code "110") (name "unconnected-(IC3-EP-Pad9)") (class "Default")
      (node (ref "IC3") (pin "9") (pinfunction "EP_9") (pintype "bidirectional"))
    )
    (net (code "111") (name "unconnected-(IC3-SYNCH-Pad2)") (class "Default")
      (node (ref "IC3") (pin "2") (pinfunction "SYNCH_2") (pintype "bidirectional"))
    )
    (net (code "112") (name "unconnected-(RADIO-G1-Pad10)") (class "Default")
      (node (ref "RADIO") (pin "10") (pinfunction "G1_10") (pintype "bidirectional"))
    )
    (net (code "113") (name "unconnected-(RADIO-G2-Pad11)") (class "Default")
      (node (ref "RADIO") (pin "11") (pinfunction "G2_11") (pintype "bidirectional"))
    )
    (net (code "114") (name "unconnected-(RADIO-G3-Pad12)") (class "Default")
      (node (ref "RADIO") (pin "12") (pinfunction "G3_12") (pintype "bidirectional"))
    )
    (net (code "115") (name "unconnected-(RADIO-G4-Pad13)") (class "Default")
      (node (ref "RADIO") (pin "13") (pinfunction "G4_13") (pintype "bidirectional"))
    )
    (net (code "116") (name "unconnected-(RADIO-G5-Pad14)") (class "Default")
      (node (ref "RADIO") (pin "14") (pinfunction "G5_14") (pintype "bidirectional"))
    )
    (net (code "117") (name "unconnected-(TEENSY4.1-5V-Pad+5V)") (class "Default")
      (node (ref "TEENSY4.1") (pin "+5V") (pinfunction "5V_+5V") (pintype "bidirectional"))
    )
    (net (code "118") (name "unconnected-(TEENSY4.1-Pad3V3-2)") (class "Default")
      (node (ref "TEENSY4.1") (pin "3V3-2") (pinfunction "3V3-2_3V3-2") (pintype "bidirectional"))
    )
    (net (code "119") (name "unconnected-(TEENSY4.1-PadD+)") (class "Default")
      (node (ref "TEENSY4.1") (pin "D+") (pinfunction "D+_D+") (pintype "bidirectional"))
    )
    (net (code "120") (name "unconnected-(TEENSY4.1-PadD-)") (class "Default")
      (node (ref "TEENSY4.1") (pin "D-") (pinfunction "D-_D-") (pintype "bidirectional"))
    )
    (net (code "121") (name "unconnected-(TEENSY4.1-PadDM)") (class "Default")
      (node (ref "TEENSY4.1") (pin "DM") (pinfunction "DM_DM") (pintype "bidirectional"))
    )
    (net (code "122") (name "unconnected-(TEENSY4.1-PadDP)") (class "Default")
      (node (ref "TEENSY4.1") (pin "DP") (pinfunction "DP_DP") (pintype "bidirectional"))
    )
    (net (code "123") (name "unconnected-(TEENSY4.1-PadG)") (class "Default")
      (node (ref "TEENSY4.1") (pin "G") (pinfunction "G_G") (pintype "bidirectional"))
    )
    (net (code "124") (name "unconnected-(TEENSY4.1-PadGND2)") (class "Default")
      (node (ref "TEENSY4.1") (pin "GND2") (pinfunction "GND2_GND2") (pintype "bidirectional"))
    )
    (net (code "125") (name "unconnected-(TEENSY4.1-PadGND4)") (class "Default")
      (node (ref "TEENSY4.1") (pin "GND4") (pinfunction "GND4_GND4") (pintype "bidirectional"))
    )
    (net (code "126") (name "unconnected-(TEENSY4.1-PadGND5)") (class "Default")
      (node (ref "TEENSY4.1") (pin "GND5") (pinfunction "GND5_GND5") (pintype "bidirectional"))
    )
    (net (code "127") (name "unconnected-(TEENSY4.1-PadLED)") (class "Default")
      (node (ref "TEENSY4.1") (pin "LED") (pinfunction "LED_LED") (pintype "bidirectional"))
    )
    (net (code "128") (name "unconnected-(TEENSY4.1-PadON{slash}OFF)") (class "Default")
      (node (ref "TEENSY4.1") (pin "ON/OFF") (pinfunction "ON/OFF_ON/OFF") (pintype "bidirectional"))
    )
    (net (code "129") (name "unconnected-(TEENSY4.1-PadPROGRAM)") (class "Default")
      (node (ref "TEENSY4.1") (pin "PROGRAM") (pinfunction "PROGRAM_PROGRAM") (pintype "bidirectional"))
    )
    (net (code "130") (name "unconnected-(TEENSY4.1-PadR+)") (class "Default")
      (node (ref "TEENSY4.1") (pin "R+") (pinfunction "R+_R+") (pintype "bidirectional"))
    )
    (net (code "131") (name "unconnected-(TEENSY4.1-PadR-)") (class "Default")
      (node (ref "TEENSY4.1") (pin "R-") (pinfunction "R-_R-") (pintype "bidirectional"))
    )
    (net (code "132") (name "unconnected-(TEENSY4.1-PadT+)") (class "Default")
      (node (ref "TEENSY4.1") (pin "T+") (pinfunction "T+_T+") (pintype "bidirectional"))
    )
    (net (code "133") (name "unconnected-(TEENSY4.1-PadT-)") (class "Default")
      (node (ref "TEENSY4.1") (pin "T-") (pinfunction "T-_T-") (pintype "bidirectional"))
    )
    (net (code "134") (name "unconnected-(TEENSY4.1-PadVBAT)") (class "Default")
      (node (ref "TEENSY4.1") (pin "VBAT") (pinfunction "VBAT_VBAT") (pintype "bidirectional"))
    )
    (net (code "135") (name "unconnected-(TEENSY4.1-PadVUSB)") (class "Default")
      (node (ref "TEENSY4.1") (pin "VUSB") (pinfunction "VUSB_VUSB") (pintype "bidirectional"))
    )
    (net (code "136") (name "unconnected-(UNUSED_PINS3-Pad1)") (class "Default")
      (node (ref "UNUSED_PINS3") (pin "1") (pinfunction "1_1") (pintype "passive"))
    )
  )
)
